# Uc_Ticketing_Slave.net
KiCad netlist of a schematic drawn in Altium Designer
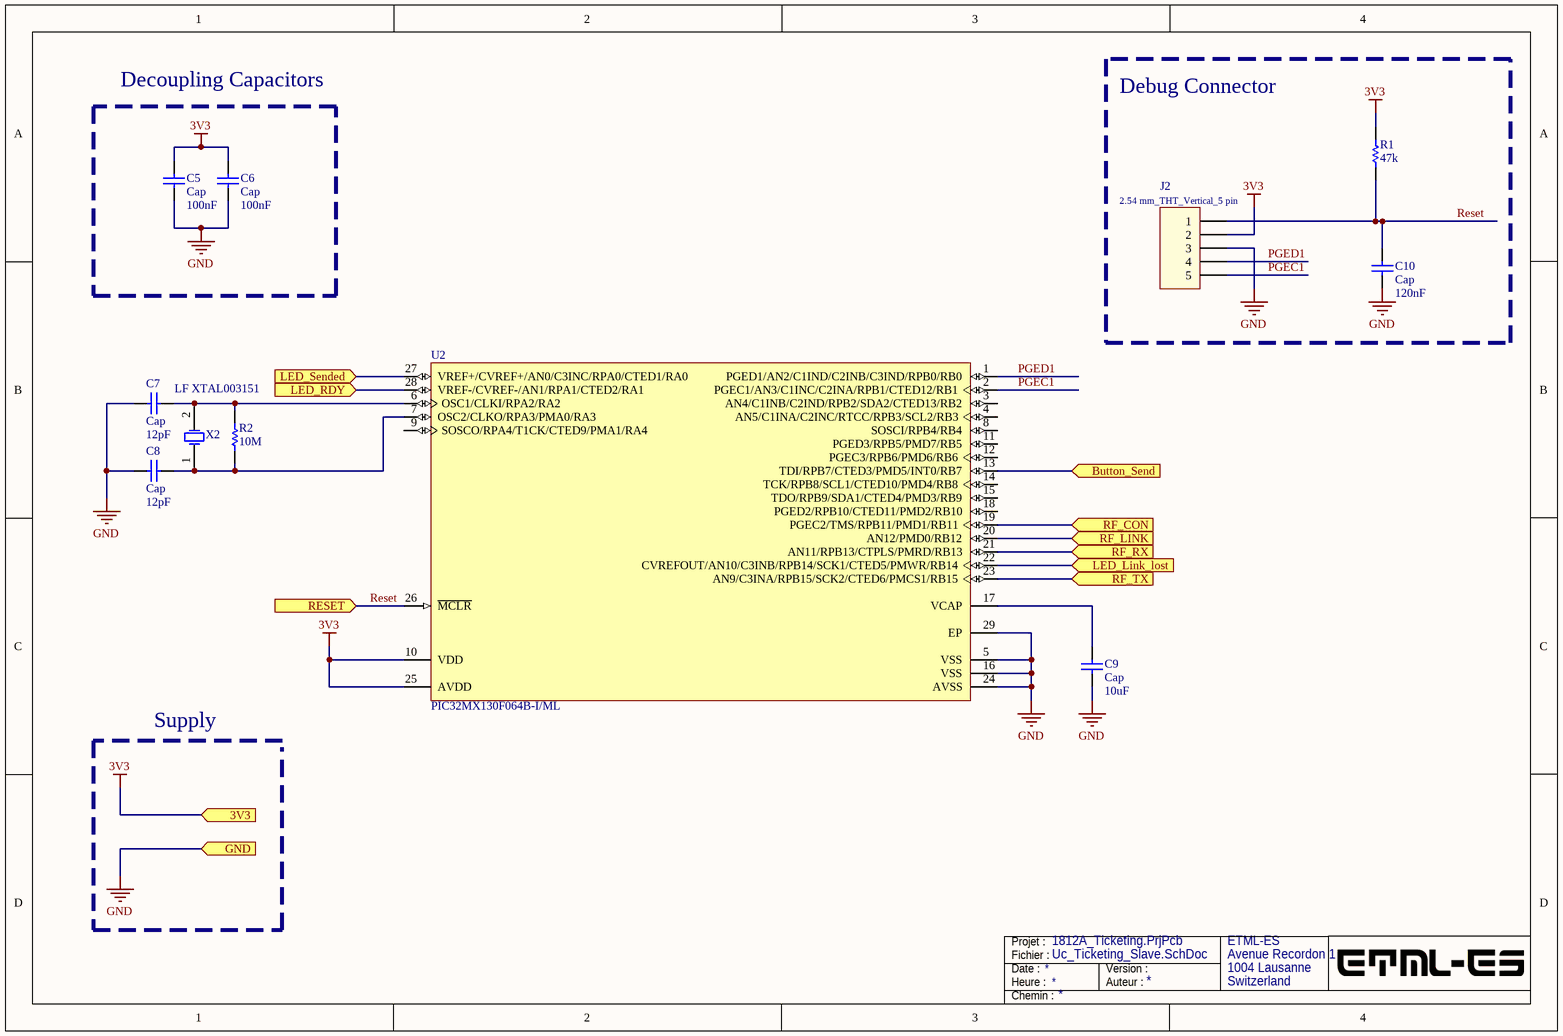
[diagram p0: Uc_Ticketing_Slave.SchDoc]

(export (version "E")
  (design (tool "Eeschema 10.0.6"))
  (components
    (comp (ref "C5")
      (value "Cap")
      (footprint "6-0805_N")
      (description "Capacitor")
      (fields (field (name "ALTIUM_VALUE") "100nF") (field (name "PUBLISHER") "Altium Limited"))
      (libsource (lib "Miscellaneous Devices") (part "Cap"))
    )
    (comp (ref "C6")
      (value "Cap")
      (footprint "6-0805_N")
      (description "Capacitor")
      (fields (field (name "ALTIUM_VALUE") "100nF") (field (name "PUBLISHER") "Altium Limited"))
      (libsource (lib "Miscellaneous Devices") (part "Cap"))
    )
    (comp (ref "C7")
      (value "Cap")
      (footprint "6-0805_N")
      (description "Capacitor")
      (fields (field (name "ALTIUM_VALUE") "12pF") (field (name "PUBLISHER") "Altium Limited"))
      (libsource (lib "Miscellaneous Devices") (part "Cap"))
    )
    (comp (ref "C8")
      (value "Cap")
      (footprint "6-0805_N")
      (description "Capacitor")
      (fields (field (name "ALTIUM_VALUE") "12pF") (field (name "PUBLISHER") "Altium Limited"))
      (libsource (lib "Miscellaneous Devices") (part "Cap"))
    )
    (comp (ref "C9")
      (value "Cap")
      (footprint "6-0805_N")
      (description "Capacitor")
      (fields (field (name "ALTIUM_VALUE") "10uF") (field (name "PUBLISHER") "Altium Limited"))
      (libsource (lib "Miscellaneous Devices") (part "Cap"))
    )
    (comp (ref "C10")
      (value "Cap")
      (footprint "6-0805_N")
      (description "Capacitor")
      (fields (field (name "ALTIUM_VALUE") "120nF") (field (name "PUBLISHER") "Altium Limited"))
      (libsource (lib "Miscellaneous Devices") (part "Cap"))
    )
    (comp (ref "J2")
      (value "2.54 mm_THT_Vertical_5 pin")
      (footprint "61300511121")
      (description "Pin Header WR-PHD, pitch 2.54 mm, THT, Vertical, single row, 5 pin")
      (fields (field (name "PART NUMBER") "61300511121") (field (name "PUBLISHER") "Wurth Elektronik"))
      (libsource (lib "ALTIUM-PHD_2_54_THT_PIN_HEADER_6130XX11121-rev18a") (part "61300511121"))
    )
    (comp (ref "R1")
      (value "47k")
      (footprint "RESC0805(2012)_L")
      (description "100K 0.125W 5% 0805 (2012 Metric)  SMD")
      (fields (field (name "TOLERANCE") "5 %") (field (name "POWER") "0.125 W"))
      (libsource (lib "Altium Content Vault") (part "CMP-1013-00122-1"))
    )
    (comp (ref "R2")
      (value "10M")
      (footprint "RESC0805(2012)_L")
      (description "100K 0.125W 5% 0805 (2012 Metric)  SMD")
      (fields (field (name "TOLERANCE") "5 %") (field (name "POWER") "0.125 W"))
      (libsource (lib "Altium Content Vault") (part "CMP-1013-00122-1"))
    )
    (comp (ref "U2")
      (value "PIC32MX130F064B-I/ML")
      (footprint "MCHP-QFN-ML28_L")
      (fields (field (name "MANUFACTURER") "Microchip"))
      (libsource (lib "Altium Content Vault") (part "MCHP-PIC32MX1XXFXXXB-QFN-28"))
    )
    (comp (ref "X2")
      (value "LF XTAL003151")
      (footprint "ECS-80-18-5PX-TR_V")
      (description "Low Profile Quartz Crystal, 8.0 MHz, 2-Pin SMD, RoHS, Tape and Reel")
      (fields (field (name "TOLERANCE") "30PPM") (field (name "MANUFACTURER") "ECS"))
      (libsource (lib "Altium Content Vault") (part "XTAL_1-2-2"))
    )
  )
  (nets
    (net (code "1") (name "/Button_Send") (class "Default")
      (node (ref "U2") (pin "13") (pinfunction "TDI/RPB7/CTED3/PMD5/INT0/RB7_13") (pintype "bidirectional"))
    )
    (net (code "2") (name "/LED_Link_lost") (class "Default")
      (node (ref "U2") (pin "22") (pinfunction "CVREFOUT/AN10/C3INB/RPB14/SCK1/CTED5/PMWR/RB14_22") (pintype "bidirectional"))
    )
    (net (code "3") (name "/LED_RDY") (class "Default")
      (node (ref "U2") (pin "28") (pinfunction "VREF-/CVREF-/AN1/RPA1/CTED2/RA1_28") (pintype "bidirectional"))
    )
    (net (code "4") (name "/LED_Sended") (class "Default")
      (node (ref "U2") (pin "27") (pinfunction "VREF+/CVREF+/AN0/C3INC/RPA0/CTED1/RA0_27") (pintype "bidirectional"))
    )
    (net (code "5") (name "/PGEC1") (class "Default")
      (node (ref "J2") (pin "5") (pinfunction "5_5") (pintype "passive"))
      (node (ref "U2") (pin "2") (pinfunction "PGEC1/AN3/C1INC/C2INA/RPB1/CTED12/RB1_2") (pintype "bidirectional"))
    )
    (net (code "6") (name "/PGED1") (class "Default")
      (node (ref "J2") (pin "4") (pinfunction "4_4") (pintype "passive"))
      (node (ref "U2") (pin "1") (pinfunction "PGED1/AN2/C1IND/C2INB/C3IND/RPB0/RB0_1") (pintype "bidirectional"))
    )
    (net (code "7") (name "/RF_CON") (class "Default")
      (node (ref "U2") (pin "19") (pinfunction "PGEC2/TMS/RPB11/PMD1/RB11_19") (pintype "bidirectional"))
    )
    (net (code "8") (name "/RF_LINK") (class "Default")
      (node (ref "U2") (pin "20") (pinfunction "AN12/PMD0/RB12_20") (pintype "bidirectional"))
    )
    (net (code "9") (name "/RF_RX") (class "Default")
      (node (ref "U2") (pin "21") (pinfunction "AN11/RPB13/CTPLS/PMRD/RB13_21") (pintype "bidirectional"))
    )
    (net (code "10") (name "/RF_TX") (class "Default")
      (node (ref "U2") (pin "23") (pinfunction "AN9/C3INA/RPB15/SCK2/CTED6/PMCS1/RB15_23") (pintype "bidirectional"))
    )
    (net (code "11") (name "/Reset") (class "Default")
      (node (ref "C10") (pin "2") (pinfunction "2_2") (pintype "passive"))
      (node (ref "J2") (pin "1") (pinfunction "1_1") (pintype "passive"))
      (node (ref "R1") (pin "2") (pinfunction "2_2") (pintype "passive"))
      (node (ref "U2") (pin "26") (pinfunction "~{MCLR}_26") (pintype "input"))
    )
    (net (code "12") (name "3V3") (class "Default")
      (node (ref "C5") (pin "2") (pinfunction "2_2") (pintype "passive"))
      (node (ref "C6") (pin "2") (pinfunction "2_2") (pintype "passive"))
      (node (ref "J2") (pin "2") (pinfunction "2_2") (pintype "passive"))
      (node (ref "R1") (pin "1") (pinfunction "1_1") (pintype "passive"))
      (node (ref "U2") (pin "10") (pinfunction "VDD_10") (pintype "power_in"))
      (node (ref "U2") (pin "25") (pinfunction "AVDD_25") (pintype "power_in"))
    )
    (net (code "13") (name "GND") (class "Default")
      (node (ref "C10") (pin "1") (pinfunction "1_1") (pintype "passive"))
      (node (ref "C5") (pin "1") (pinfunction "1_1") (pintype "passive"))
      (node (ref "C6") (pin "1") (pinfunction "1_1") (pintype "passive"))
      (node (ref "C7") (pin "1") (pinfunction "1_1") (pintype "passive"))
      (node (ref "C8") (pin "2") (pinfunction "2_2") (pintype "passive"))
      (node (ref "C9") (pin "1") (pinfunction "1_1") (pintype "passive"))
      (node (ref "J2") (pin "3") (pinfunction "3_3") (pintype "passive"))
      (node (ref "U2") (pin "16") (pinfunction "VSS_16") (pintype "power_in"))
      (node (ref "U2") (pin "24") (pinfunction "AVSS_24") (pintype "power_in"))
      (node (ref "U2") (pin "29") (pinfunction "EP_29") (pintype "passive"))
      (node (ref "U2") (pin "5") (pinfunction "VSS_5") (pintype "power_in"))
    )
    (net (code "14") (name "Net-(U2-OSC1{slash}CLKI{slash}RPA2{slash}RA2)") (class "Default")
      (node (ref "C7") (pin "2") (pinfunction "2_2") (pintype "passive"))
      (node (ref "R2") (pin "2") (pinfunction "2_2") (pintype "passive"))
      (node (ref "U2") (pin "6") (pinfunction "OSC1/CLKI/RPA2/RA2_6") (pintype "bidirectional"))
      (node (ref "X2") (pin "2") (pinfunction "X2_2") (pintype "passive"))
    )
    (net (code "15") (name "Net-(U2-OSC2{slash}CLKO{slash}RPA3{slash}PMA0{slash}RA3)") (class "Default")
      (node (ref "C8") (pin "1") (pinfunction "1_1") (pintype "passive"))
      (node (ref "R2") (pin "1") (pinfunction "1_1") (pintype "passive"))
      (node (ref "U2") (pin "7") (pinfunction "OSC2/CLKO/RPA3/PMA0/RA3_7") (pintype "bidirectional"))
      (node (ref "X2") (pin "1") (pinfunction "X1_1") (pintype "passive"))
    )
    (net (code "16") (name "Net-(U2-VCAP)") (class "Default")
      (node (ref "C9") (pin "2") (pinfunction "2_2") (pintype "passive"))
      (node (ref "U2") (pin "17") (pinfunction "VCAP_17") (pintype "passive"))
    )
    (net (code "17") (name "unconnected-(U2-AN4{slash}C1INB{slash}C2IND{slash}RPB2{slash}SDA2{slash}CTED13{slash}RB2-Pad3)") (class "Default")
      (node (ref "U2") (pin "3") (pinfunction "AN4/C1INB/C2IND/RPB2/SDA2/CTED13/RB2_3") (pintype "bidirectional"))
    )
    (net (code "18") (name "unconnected-(U2-AN5{slash}C1INA{slash}C2INC{slash}RTCC{slash}RPB3{slash}SCL2{slash}RB3-Pad4)") (class "Default")
      (node (ref "U2") (pin "4") (pinfunction "AN5/C1INA/C2INC/RTCC/RPB3/SCL2/RB3_4") (pintype "bidirectional"))
    )
    (net (code "19") (name "unconnected-(U2-PGEC3{slash}RPB6{slash}PMD6{slash}RB6-Pad12)") (class "Default")
      (node (ref "U2") (pin "12") (pinfunction "PGEC3/RPB6/PMD6/RB6_12") (pintype "bidirectional"))
    )
    (net (code "20") (name "unconnected-(U2-PGED2{slash}RPB10{slash}CTED11{slash}PMD2{slash}RB10-Pad18)") (class "Default")
      (node (ref "U2") (pin "18") (pinfunction "PGED2/RPB10/CTED11/PMD2/RB10_18") (pintype "bidirectional"))
    )
    (net (code "21") (name "unconnected-(U2-PGED3{slash}RPB5{slash}PMD7{slash}RB5-Pad11)") (class "Default")
      (node (ref "U2") (pin "11") (pinfunction "PGED3/RPB5/PMD7/RB5_11") (pintype "bidirectional"))
    )
    (net (code "22") (name "unconnected-(U2-SOSCI{slash}RPB4{slash}RB4-Pad8)") (class "Default")
      (node (ref "U2") (pin "8") (pinfunction "SOSCI/RPB4/RB4_8") (pintype "bidirectional"))
    )
    (net (code "23") (name "unconnected-(U2-SOSCO{slash}RPA4{slash}T1CK{slash}CTED9{slash}PMA1{slash}RA4-Pad9)") (class "Default")
      (node (ref "U2") (pin "9") (pinfunction "SOSCO/RPA4/T1CK/CTED9/PMA1/RA4_9") (pintype "bidirectional"))
    )
    (net (code "24") (name "unconnected-(U2-TCK{slash}RPB8{slash}SCL1{slash}CTED10{slash}PMD4{slash}RB8-Pad14)") (class "Default")
      (node (ref "U2") (pin "14") (pinfunction "TCK/RPB8/SCL1/CTED10/PMD4/RB8_14") (pintype "bidirectional"))
    )
    (net (code "25") (name "unconnected-(U2-TDO{slash}RPB9{slash}SDA1{slash}CTED4{slash}PMD3{slash}RB9-Pad15)") (class "Default")
      (node (ref "U2") (pin "15") (pinfunction "TDO/RPB9/SDA1/CTED4/PMD3/RB9_15") (pintype "bidirectional"))
    )
  )
)
